# tilt_soms_lgbu.net
KiCad netlist of a schematic drawn in EAGLE
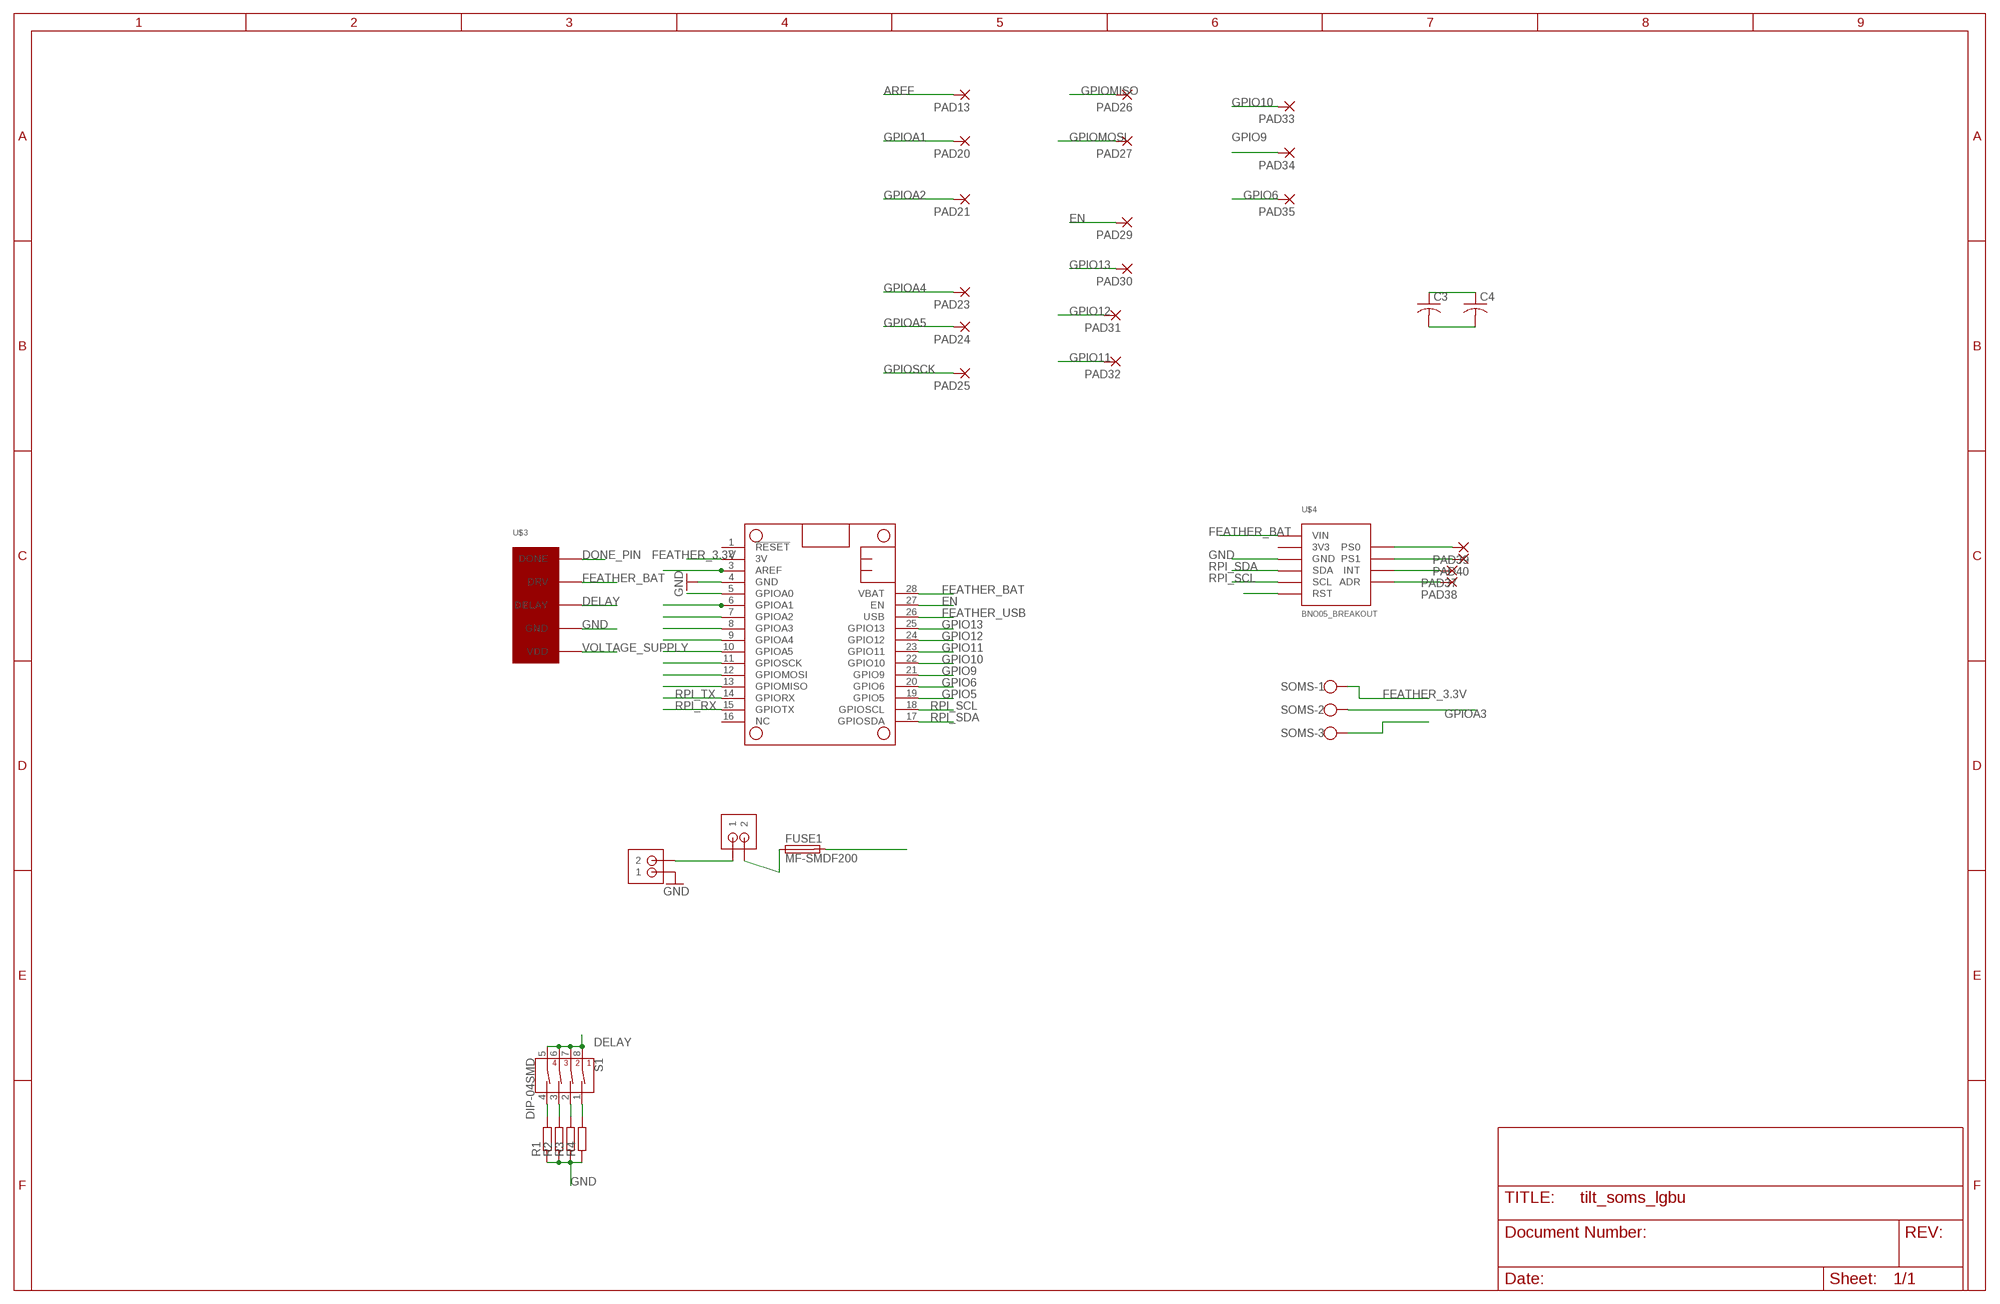
[diagram p0: schematic, sheet 1]

(export (version "E")
  (design (tool "Eeschema 10.0.6"))
  (components
    (comp (ref "BATT")
      (value "JST-PH_2-PIN_HEADER")
      (footprint "eagle-import:JST_B2B-PH_HEADER")
      (libsource (lib "eagle-import") (part "JST-PH_2-PIN_HEADER"))
    )
    (comp (ref "C3")
      (value "C-USC1812")
      (footprint "eagle-import:C1812")
      (libsource (lib "eagle-import") (part "C-USC1812"))
    )
    (comp (ref "C4")
      (value "C-USC1812")
      (footprint "eagle-import:C1812")
      (libsource (lib "eagle-import") (part "C-USC1812"))
    )
    (comp (ref "FUSE1")
      (value "MF-SMDF200")
      (footprint "eagle-import:MF-SMDF050")
      (libsource (lib "eagle-import") (part "MF-SMDF200"))
    )
    (comp (ref "MAIN_SWITCH")
      (value "JST-PH_2-PIN_HEADER")
      (footprint "eagle-import:JST_B2B-PH_HEADER")
      (libsource (lib "eagle-import") (part "JST-PH_2-PIN_HEADER"))
    )
    (comp (ref "MS1")
      (value "FEATHERWING_NODIM")
      (footprint "eagle-import:FEATHERWING_DIM")
      (libsource (lib "eagle-import") (part "FEATHERWING_NODIM"))
    )
    (comp (ref "PAD13")
      (value "WIREPADSMD1,27-254")
      (footprint "eagle-import:SMD1,27-2,54")
      (libsource (lib "eagle-import") (part "WIREPADSMD1,27-254"))
    )
    (comp (ref "PAD20")
      (value "WIREPADSMD1,27-254")
      (footprint "eagle-import:SMD1,27-2,54")
      (libsource (lib "eagle-import") (part "WIREPADSMD1,27-254"))
    )
    (comp (ref "PAD21")
      (value "WIREPADSMD1,27-254")
      (footprint "eagle-import:SMD1,27-2,54")
      (libsource (lib "eagle-import") (part "WIREPADSMD1,27-254"))
    )
    (comp (ref "PAD23")
      (value "WIREPADSMD1,27-254")
      (footprint "eagle-import:SMD1,27-2,54")
      (libsource (lib "eagle-import") (part "WIREPADSMD1,27-254"))
    )
    (comp (ref "PAD24")
      (value "WIREPADSMD1,27-254")
      (footprint "eagle-import:SMD1,27-2,54")
      (libsource (lib "eagle-import") (part "WIREPADSMD1,27-254"))
    )
    (comp (ref "PAD25")
      (value "WIREPADSMD1,27-254")
      (footprint "eagle-import:SMD1,27-2,54")
      (libsource (lib "eagle-import") (part "WIREPADSMD1,27-254"))
    )
    (comp (ref "PAD26")
      (value "WIREPADSMD1,27-254")
      (footprint "eagle-import:SMD1,27-2,54")
      (libsource (lib "eagle-import") (part "WIREPADSMD1,27-254"))
    )
    (comp (ref "PAD27")
      (value "WIREPADSMD1,27-254")
      (footprint "eagle-import:SMD1,27-2,54")
      (libsource (lib "eagle-import") (part "WIREPADSMD1,27-254"))
    )
    (comp (ref "PAD29")
      (value "WIREPADSMD1,27-254")
      (footprint "eagle-import:SMD1,27-2,54")
      (libsource (lib "eagle-import") (part "WIREPADSMD1,27-254"))
    )
    (comp (ref "PAD30")
      (value "WIREPADSMD1,27-254")
      (footprint "eagle-import:SMD1,27-2,54")
      (libsource (lib "eagle-import") (part "WIREPADSMD1,27-254"))
    )
    (comp (ref "PAD31")
      (value "WIREPADSMD1,27-254")
      (footprint "eagle-import:SMD1,27-2,54")
      (libsource (lib "eagle-import") (part "WIREPADSMD1,27-254"))
    )
    (comp (ref "PAD32")
      (value "WIREPADSMD1,27-254")
      (footprint "eagle-import:SMD1,27-2,54")
      (libsource (lib "eagle-import") (part "WIREPADSMD1,27-254"))
    )
    (comp (ref "PAD33")
      (value "WIREPADSMD1,27-254")
      (footprint "eagle-import:SMD1,27-2,54")
      (libsource (lib "eagle-import") (part "WIREPADSMD1,27-254"))
    )
    (comp (ref "PAD34")
      (value "WIREPADSMD1,27-254")
      (footprint "eagle-import:SMD1,27-2,54")
      (libsource (lib "eagle-import") (part "WIREPADSMD1,27-254"))
    )
    (comp (ref "PAD35")
      (value "WIREPADSMD1,27-254")
      (footprint "eagle-import:SMD1,27-2,54")
      (libsource (lib "eagle-import") (part "WIREPADSMD1,27-254"))
    )
    (comp (ref "PAD37")
      (value "WIREPADSMD1,27-254")
      (footprint "eagle-import:SMD1,27-2,54")
      (libsource (lib "eagle-import") (part "WIREPADSMD1,27-254"))
    )
    (comp (ref "PAD38")
      (value "WIREPADSMD1,27-254")
      (footprint "eagle-import:SMD1,27-2,54")
      (libsource (lib "eagle-import") (part "WIREPADSMD1,27-254"))
    )
    (comp (ref "PAD39")
      (value "WIREPADSMD1,27-254")
      (footprint "eagle-import:SMD1,27-2,54")
      (libsource (lib "eagle-import") (part "WIREPADSMD1,27-254"))
    )
    (comp (ref "PAD40")
      (value "WIREPADSMD1,27-254")
      (footprint "eagle-import:SMD1,27-2,54")
      (libsource (lib "eagle-import") (part "WIREPADSMD1,27-254"))
    )
    (comp (ref "R1")
      (value "R-EU_0204/5")
      (footprint "eagle-import:0204_5")
      (libsource (lib "eagle-import") (part "R-EU_0204/5"))
    )
    (comp (ref "R2")
      (value "R-EU_0204/5")
      (footprint "eagle-import:0204_5")
      (libsource (lib "eagle-import") (part "R-EU_0204/5"))
    )
    (comp (ref "R3")
      (value "R-EU_0204/5")
      (footprint "eagle-import:0204_5")
      (libsource (lib "eagle-import") (part "R-EU_0204/5"))
    )
    (comp (ref "R4")
      (value "R-EU_0204/5")
      (footprint "eagle-import:0204_5")
      (libsource (lib "eagle-import") (part "R-EU_0204/5"))
    )
    (comp (ref "S1")
      (value "DIP-04SMD")
      (footprint "eagle-import:DIPSWITCH-04-SMD")
      (libsource (lib "eagle-import") (part "DIP-04SMD"))
    )
    (comp (ref "SOMS")
      (value "W237-103")
      (footprint "eagle-import:W237-103")
      (fields (field (name "MPN") "237-103"))
      (libsource (lib "eagle-import") (part "W237-103"))
    )
    (comp (ref "U$3")
      (value "TPL5110_BREAKOUT")
      (footprint "eagle-import:TPL5110_BREAKOUT")
      (libsource (lib "eagle-import") (part "TPL5110_BREAKOUT"))
    )
    (comp (ref "U$4")
      (value "BNO05_BREAKOUT")
      (footprint "eagle-import:BNO05_BREAKOUT")
      (libsource (lib "eagle-import") (part "BNO05_BREAKOUT"))
    )
  )
  (nets
    (net (code "1") (name "/AREF") (class "Default")
      (node (ref "MS1") (pin "3") (pinfunction "AREF_3") (pintype "passive"))
      (node (ref "PAD13") (pin "1") (pinfunction "P_1") (pintype "passive"))
    )
    (net (code "2") (name "/DELAY") (class "Default")
      (node (ref "S1") (pin "5") (pinfunction "4B_5") (pintype "bidirectional"))
      (node (ref "S1") (pin "6") (pinfunction "3B_6") (pintype "bidirectional"))
      (node (ref "S1") (pin "7") (pinfunction "2B_7") (pintype "bidirectional"))
      (node (ref "S1") (pin "8") (pinfunction "1B_8") (pintype "bidirectional"))
      (node (ref "U$3") (pin "DELAY") (pinfunction "DELAY_DELAY") (pintype "bidirectional"))
    )
    (net (code "3") (name "/DONE_PIN") (class "Default")
      (node (ref "MS1") (pin "5") (pinfunction "GPIOA0_5") (pintype "bidirectional"))
      (node (ref "U$3") (pin "DONE") (pinfunction "DONE_DONE") (pintype "bidirectional"))
    )
    (net (code "4") (name "/EN") (class "Default")
      (node (ref "MS1") (pin "27") (pinfunction "EN_27") (pintype "passive"))
      (node (ref "PAD29") (pin "1") (pinfunction "P_1") (pintype "passive"))
    )
    (net (code "5") (name "/FEATHER_3.3V") (class "Default")
      (node (ref "MS1") (pin "2") (pinfunction "3V_2") (pintype "power_in"))
      (node (ref "SOMS") (pin "1") (pinfunction "KL_1") (pintype "passive"))
    )
    (net (code "6") (name "/FEATHER_BAT") (class "Default")
      (node (ref "MS1") (pin "28") (pinfunction "VBAT_28") (pintype "power_in"))
      (node (ref "U$3") (pin "DRV") (pinfunction "DRV_DRV") (pintype "power_in"))
      (node (ref "U$4") (pin "VIN") (pinfunction "VIN_VIN") (pintype "power_in"))
    )
    (net (code "7") (name "/FEATHER_USB") (class "Default")
      (node (ref "MS1") (pin "26") (pinfunction "USB_26") (pintype "power_in"))
    )
    (net (code "8") (name "/GPIO5") (class "Default")
      (node (ref "MS1") (pin "19") (pinfunction "GPIO5_19") (pintype "bidirectional"))
      (node (ref "U$4") (pin "RST") (pinfunction "RST_RST") (pintype "bidirectional"))
    )
    (net (code "9") (name "/GPIO6") (class "Default")
      (node (ref "MS1") (pin "20") (pinfunction "GPIO6_20") (pintype "bidirectional"))
      (node (ref "PAD35") (pin "1") (pinfunction "P_1") (pintype "passive"))
    )
    (net (code "10") (name "/GPIO9") (class "Default")
      (node (ref "MS1") (pin "21") (pinfunction "GPIO9_21") (pintype "bidirectional"))
      (node (ref "PAD34") (pin "1") (pinfunction "P_1") (pintype "passive"))
    )
    (net (code "11") (name "/GPIO10") (class "Default")
      (node (ref "MS1") (pin "22") (pinfunction "GPIO10_22") (pintype "bidirectional"))
      (node (ref "PAD33") (pin "1") (pinfunction "P_1") (pintype "passive"))
    )
    (net (code "12") (name "/GPIO11") (class "Default")
      (node (ref "MS1") (pin "23") (pinfunction "GPIO11_23") (pintype "bidirectional"))
      (node (ref "PAD32") (pin "1") (pinfunction "P_1") (pintype "passive"))
    )
    (net (code "13") (name "/GPIO12") (class "Default")
      (node (ref "MS1") (pin "24") (pinfunction "GPIO12_24") (pintype "bidirectional"))
      (node (ref "PAD31") (pin "1") (pinfunction "P_1") (pintype "passive"))
    )
    (net (code "14") (name "/GPIO13") (class "Default")
      (node (ref "MS1") (pin "25") (pinfunction "GPIO13_25") (pintype "bidirectional"))
      (node (ref "PAD30") (pin "1") (pinfunction "P_1") (pintype "passive"))
    )
    (net (code "15") (name "/GPIOA1") (class "Default")
      (node (ref "MS1") (pin "6") (pinfunction "GPIOA1_6") (pintype "bidirectional"))
      (node (ref "PAD20") (pin "1") (pinfunction "P_1") (pintype "passive"))
    )
    (net (code "16") (name "/GPIOA2") (class "Default")
      (node (ref "MS1") (pin "7") (pinfunction "GPIOA2_7") (pintype "bidirectional"))
      (node (ref "PAD21") (pin "1") (pinfunction "P_1") (pintype "passive"))
    )
    (net (code "17") (name "/GPIOA3") (class "Default")
      (node (ref "MS1") (pin "8") (pinfunction "GPIOA3_8") (pintype "bidirectional"))
      (node (ref "SOMS") (pin "2") (pinfunction "KL_2") (pintype "passive"))
    )
    (net (code "18") (name "/GPIOA4") (class "Default")
      (node (ref "MS1") (pin "9") (pinfunction "GPIOA4_9") (pintype "bidirectional"))
      (node (ref "PAD23") (pin "1") (pinfunction "P_1") (pintype "passive"))
    )
    (net (code "19") (name "/GPIOA5") (class "Default")
      (node (ref "MS1") (pin "10") (pinfunction "GPIOA5_10") (pintype "bidirectional"))
      (node (ref "PAD24") (pin "1") (pinfunction "P_1") (pintype "passive"))
    )
    (net (code "20") (name "/GPIOMISO") (class "Default")
      (node (ref "MS1") (pin "13") (pinfunction "GPIOMISO_13") (pintype "bidirectional"))
      (node (ref "PAD26") (pin "1") (pinfunction "P_1") (pintype "passive"))
    )
    (net (code "21") (name "/GPIOMOSI") (class "Default")
      (node (ref "MS1") (pin "12") (pinfunction "GPIOMOSI_12") (pintype "bidirectional"))
      (node (ref "PAD27") (pin "1") (pinfunction "P_1") (pintype "passive"))
    )
    (net (code "22") (name "/GPIOSCK") (class "Default")
      (node (ref "MS1") (pin "11") (pinfunction "GPIOSCK_11") (pintype "bidirectional"))
      (node (ref "PAD25") (pin "1") (pinfunction "P_1") (pintype "passive"))
    )
    (net (code "23") (name "/RPI_RX") (class "Default")
      (node (ref "MS1") (pin "15") (pinfunction "GPIOTX_15") (pintype "bidirectional"))
    )
    (net (code "24") (name "/RPI_SCL") (class "Default")
      (node (ref "MS1") (pin "18") (pinfunction "GPIOSCL_18") (pintype "bidirectional"))
      (node (ref "U$4") (pin "SCL") (pinfunction "SCL_SCL") (pintype "bidirectional"))
    )
    (net (code "25") (name "/RPI_SDA") (class "Default")
      (node (ref "MS1") (pin "17") (pinfunction "GPIOSDA_17") (pintype "bidirectional"))
      (node (ref "U$4") (pin "SDA") (pinfunction "SDA_SDA") (pintype "bidirectional"))
    )
    (net (code "26") (name "/RPI_TX") (class "Default")
      (node (ref "MS1") (pin "14") (pinfunction "GPIORX_14") (pintype "bidirectional"))
    )
    (net (code "27") (name "/VOLTAGE_SUPPLY") (class "Default")
      (node (ref "C3") (pin "1") (pinfunction "1_1") (pintype "passive"))
      (node (ref "C4") (pin "1") (pinfunction "1_1") (pintype "passive"))
      (node (ref "FUSE1") (pin "2") (pinfunction "2_2") (pintype "passive"))
      (node (ref "U$3") (pin "VDD") (pinfunction "VDD_VDD") (pintype "power_in"))
    )
    (net (code "28") (name "GND") (class "Default")
      (node (ref "BATT") (pin "P1") (pinfunction "1_P1") (pintype "bidirectional"))
      (node (ref "C3") (pin "2") (pinfunction "2_2") (pintype "passive"))
      (node (ref "C4") (pin "2") (pinfunction "2_2") (pintype "passive"))
      (node (ref "MS1") (pin "4") (pinfunction "GND_4") (pintype "power_in"))
      (node (ref "R1") (pin "1") (pinfunction "1_1") (pintype "passive"))
      (node (ref "R2") (pin "1") (pinfunction "1_1") (pintype "passive"))
      (node (ref "R3") (pin "1") (pinfunction "1_1") (pintype "passive"))
      (node (ref "R4") (pin "1") (pinfunction "1_1") (pintype "passive"))
      (node (ref "SOMS") (pin "3") (pinfunction "KL_3") (pintype "passive"))
      (node (ref "U$3") (pin "GND") (pinfunction "GND_GND") (pintype "power_in"))
      (node (ref "U$4") (pin "GND") (pinfunction "GND_GND") (pintype "bidirectional"))
    )
    (net (code "29") (name "Net-(BATT-2)") (class "Default")
      (node (ref "BATT") (pin "P2") (pinfunction "2_P2") (pintype "bidirectional"))
      (node (ref "MAIN_SWITCH") (pin "P1") (pinfunction "1_P1") (pintype "bidirectional"))
    )
    (net (code "30") (name "Net-(MAIN_SWITCH-2)") (class "Default")
      (node (ref "FUSE1") (pin "1") (pinfunction "1_1") (pintype "passive"))
      (node (ref "MAIN_SWITCH") (pin "P2") (pinfunction "2_P2") (pintype "bidirectional"))
    )
    (net (code "31") (name "Net-(PAD37-P)") (class "Default")
      (node (ref "PAD37") (pin "1") (pinfunction "P_1") (pintype "passive"))
      (node (ref "U$4") (pin "INT") (pinfunction "INT_INT") (pintype "bidirectional"))
    )
    (net (code "32") (name "Net-(PAD38-P)") (class "Default")
      (node (ref "PAD38") (pin "1") (pinfunction "P_1") (pintype "passive"))
      (node (ref "U$4") (pin "ADR") (pinfunction "ADR_ADR") (pintype "bidirectional"))
    )
    (net (code "33") (name "Net-(PAD39-P)") (class "Default")
      (node (ref "PAD39") (pin "1") (pinfunction "P_1") (pintype "passive"))
      (node (ref "U$4") (pin "PS0") (pinfunction "PS0_PS0") (pintype "bidirectional"))
    )
    (net (code "34") (name "Net-(PAD40-P)") (class "Default")
      (node (ref "PAD40") (pin "1") (pinfunction "P_1") (pintype "passive"))
      (node (ref "U$4") (pin "PS1") (pinfunction "PS1_PS1") (pintype "bidirectional"))
    )
    (net (code "35") (name "Net-(S1-1A)") (class "Default")
      (node (ref "R4") (pin "2") (pinfunction "2_2") (pintype "passive"))
      (node (ref "S1") (pin "1") (pinfunction "1A_1") (pintype "bidirectional"))
    )
    (net (code "36") (name "Net-(S1-2A)") (class "Default")
      (node (ref "R3") (pin "2") (pinfunction "2_2") (pintype "passive"))
      (node (ref "S1") (pin "2") (pinfunction "2A_2") (pintype "bidirectional"))
    )
    (net (code "37") (name "Net-(S1-3A)") (class "Default")
      (node (ref "R2") (pin "2") (pinfunction "2_2") (pintype "passive"))
      (node (ref "S1") (pin "3") (pinfunction "3A_3") (pintype "bidirectional"))
    )
    (net (code "38") (name "Net-(S1-4A)") (class "Default")
      (node (ref "R1") (pin "2") (pinfunction "2_2") (pintype "passive"))
      (node (ref "S1") (pin "4") (pinfunction "4A_4") (pintype "bidirectional"))
    )
    (net (code "39") (name "unconnected-(MS1-NC-Pad16)") (class "Default")
      (node (ref "MS1") (pin "16") (pinfunction "NC_16") (pintype "passive"))
    )
    (net (code "40") (name "unconnected-(MS1-~{RESET}-Pad1)") (class "Default")
      (node (ref "MS1") (pin "1") (pinfunction "~{RESET}_1") (pintype "input"))
    )
    (net (code "41") (name "unconnected-(U$4-Pad3V3)") (class "Default")
      (node (ref "U$4") (pin "3V3") (pinfunction "3V3_3V3") (pintype "bidirectional"))
    )
  )
)
